# trezor_v1.net
KiCad netlist of a schematic drawn in EAGLE
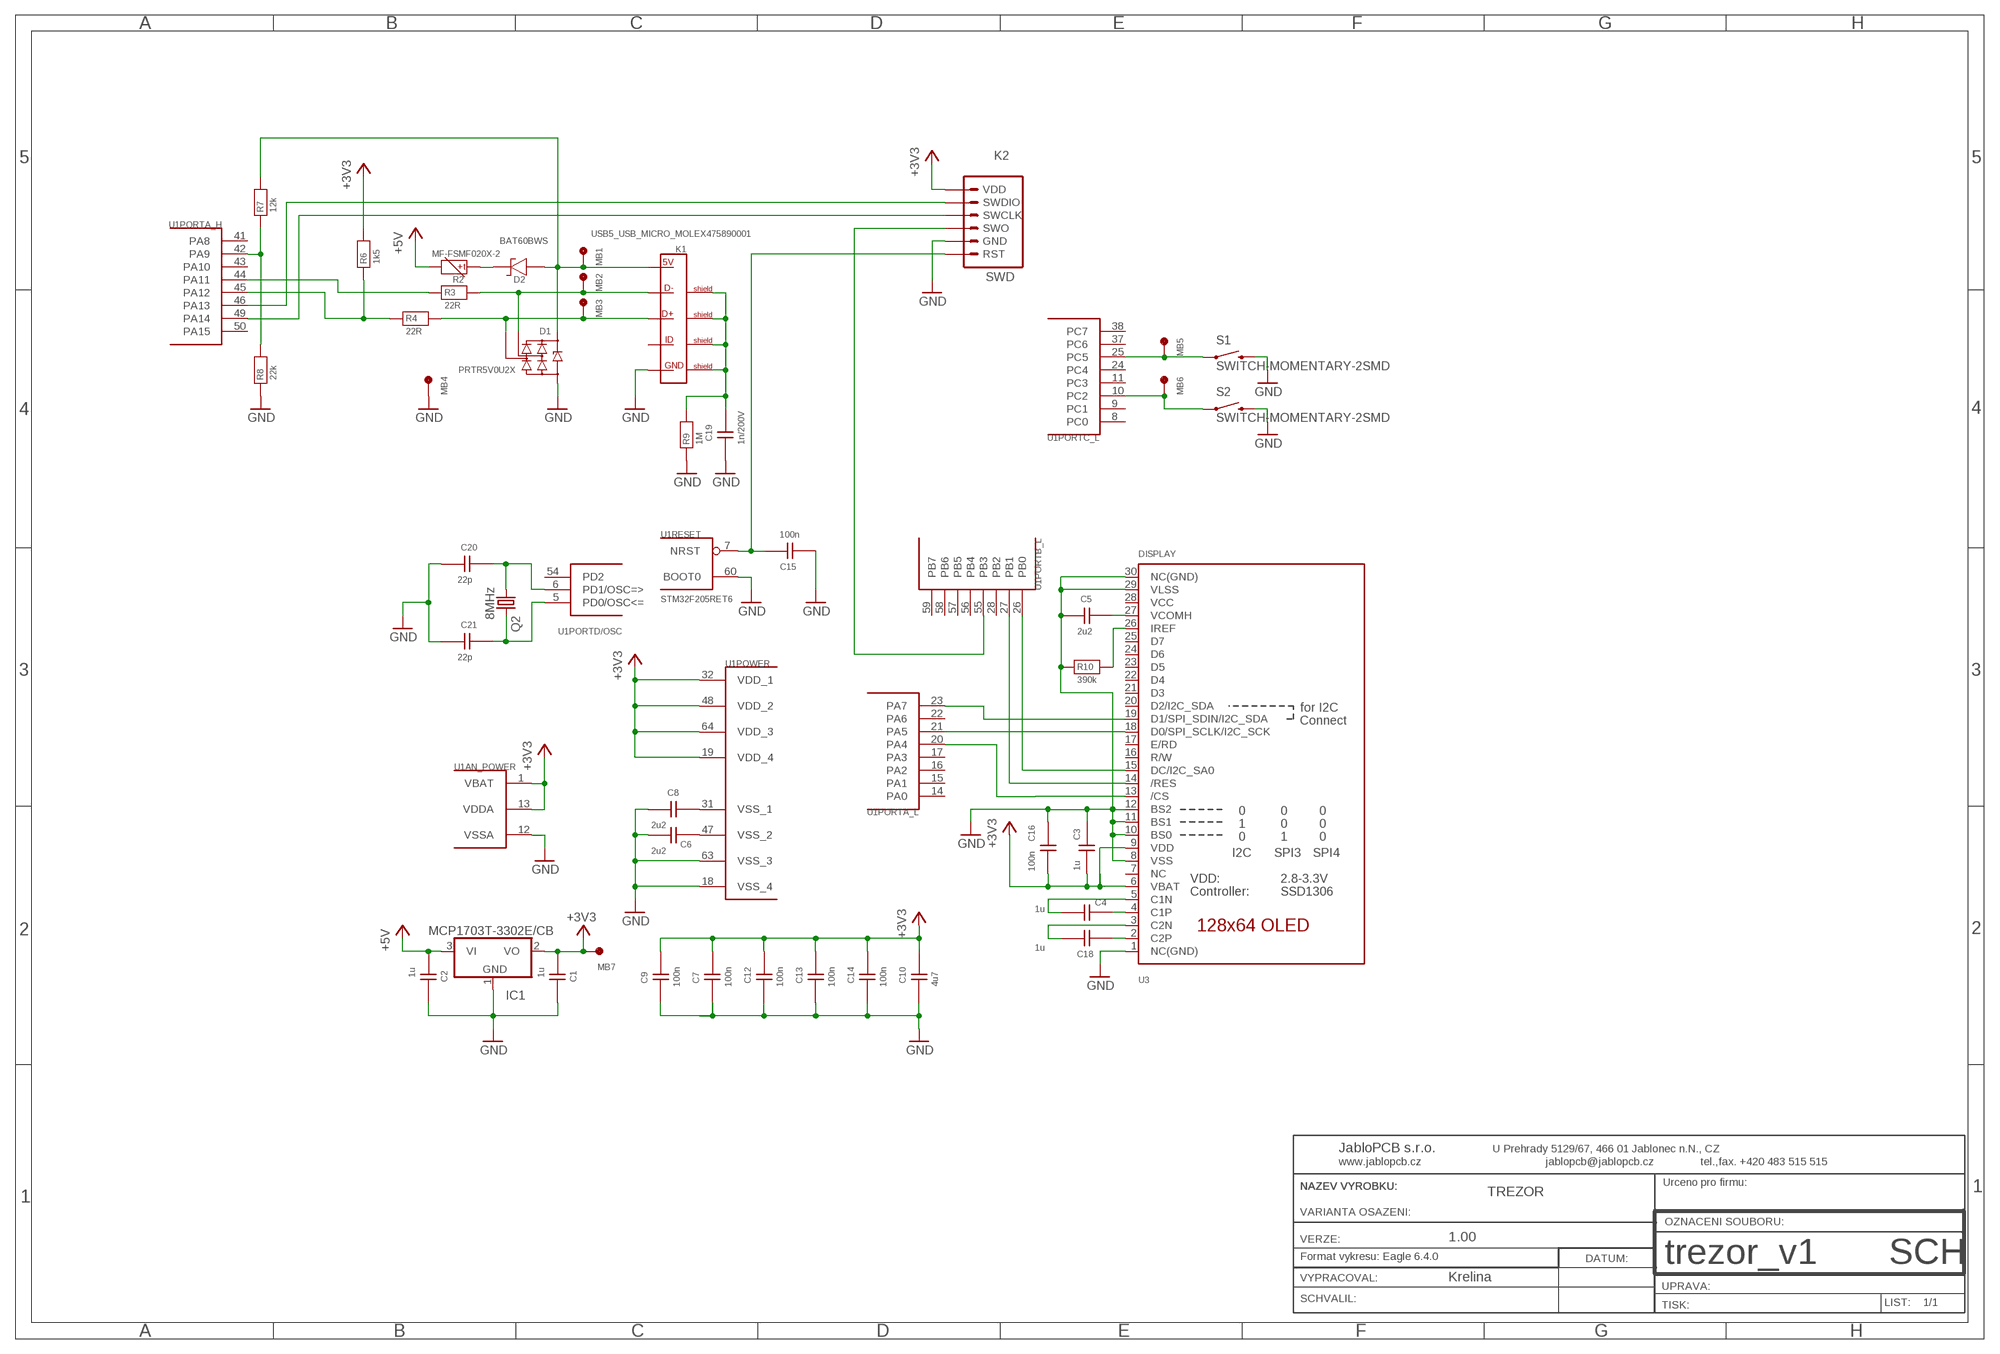
[diagram p0: schematic, sheet 1]

(export (version "E")
  (design (tool "Eeschema 10.0.6"))
  (components
    (comp (ref "C1")
      (value "1u")
      (footprint "eagle-import:0402")
      (libsource (lib "eagle-import") (part "C_0402"))
    )
    (comp (ref "C2")
      (value "1u")
      (footprint "eagle-import:0402")
      (libsource (lib "eagle-import") (part "C_0402"))
    )
    (comp (ref "C3")
      (value "1u")
      (footprint "eagle-import:0402")
      (libsource (lib "eagle-import") (part "C_0402"))
    )
    (comp (ref "C4")
      (value "1u")
      (footprint "eagle-import:0402")
      (libsource (lib "eagle-import") (part "C_0402"))
    )
    (comp (ref "C5")
      (value "2u2")
      (footprint "eagle-import:0603")
      (libsource (lib "eagle-import") (part "C_0603"))
    )
    (comp (ref "C6")
      (value "2u2")
      (footprint "eagle-import:0402")
      (libsource (lib "eagle-import") (part "C_0402"))
    )
    (comp (ref "C7")
      (value "100n")
      (footprint "eagle-import:0402")
      (libsource (lib "eagle-import") (part "C_0402"))
    )
    (comp (ref "C8")
      (value "2u2")
      (footprint "eagle-import:0402")
      (libsource (lib "eagle-import") (part "C_0402"))
    )
    (comp (ref "C9")
      (value "100n")
      (footprint "eagle-import:0402")
      (libsource (lib "eagle-import") (part "C_0402"))
    )
    (comp (ref "C10")
      (value "4u7")
      (footprint "eagle-import:0603")
      (libsource (lib "eagle-import") (part "C_0603"))
    )
    (comp (ref "C12")
      (value "100n")
      (footprint "eagle-import:0402")
      (libsource (lib "eagle-import") (part "C_0402"))
    )
    (comp (ref "C13")
      (value "100n")
      (footprint "eagle-import:0402")
      (libsource (lib "eagle-import") (part "C_0402"))
    )
    (comp (ref "C14")
      (value "100n")
      (footprint "eagle-import:0402")
      (libsource (lib "eagle-import") (part "C_0402"))
    )
    (comp (ref "C15")
      (value "100n")
      (footprint "eagle-import:0402")
      (libsource (lib "eagle-import") (part "C_0402"))
    )
    (comp (ref "C16")
      (value "100n")
      (footprint "eagle-import:0402")
      (libsource (lib "eagle-import") (part "C_0402"))
    )
    (comp (ref "C18")
      (value "1u")
      (footprint "eagle-import:0402")
      (libsource (lib "eagle-import") (part "C_0402"))
    )
    (comp (ref "C19")
      (value "1n/200V")
      (footprint "eagle-import:0603")
      (libsource (lib "eagle-import") (part "C_0603"))
    )
    (comp (ref "C20")
      (value "22p")
      (footprint "eagle-import:0402")
      (libsource (lib "eagle-import") (part "C_0402"))
    )
    (comp (ref "C21")
      (value "22p")
      (footprint "eagle-import:0402")
      (libsource (lib "eagle-import") (part "C_0402"))
    )
    (comp (ref "D1")
      (value "PRTR5V0U2X")
      (footprint "eagle-import:SOT143B")
      (libsource (lib "eagle-import") (part "PRTR5V0_SOT143B"))
    )
    (comp (ref "D2")
      (value "BAT60BWS")
      (footprint "eagle-import:SOD323")
      (libsource (lib "eagle-import") (part "DS_SOD323"))
    )
    (comp (ref "IC1")
      (value "MCP1703T-3302E/CB")
      (footprint "eagle-import:SOT23")
      (libsource (lib "eagle-import") (part "MCP1703CB"))
    )
    (comp (ref "K1")
      (value "USB5_USB_MICRO_MOLEX475890001")
      (footprint "eagle-import:USB_MICRO-MOLEX475890001")
      (libsource (lib "eagle-import") (part "USB5_USB_MICRO_MOLEX475890001"))
    )
    (comp (ref "K2")
      (value "SWD")
      (footprint "eagle-import:SWD")
      (libsource (lib "eagle-import") (part "SWD"))
    )
    (comp (ref "MB1")
      (value "MB_1.50")
      (footprint "eagle-import:MB1.5")
      (libsource (lib "eagle-import") (part "MB_1.50"))
    )
    (comp (ref "MB2")
      (value "MB_1.50")
      (footprint "eagle-import:MB1.5")
      (libsource (lib "eagle-import") (part "MB_1.50"))
    )
    (comp (ref "MB3")
      (value "MB_1.50")
      (footprint "eagle-import:MB1.5")
      (libsource (lib "eagle-import") (part "MB_1.50"))
    )
    (comp (ref "MB4")
      (value "MB_1.50")
      (footprint "eagle-import:MB1.5")
      (libsource (lib "eagle-import") (part "MB_1.50"))
    )
    (comp (ref "MB5")
      (value "MB_1.50")
      (footprint "eagle-import:MB1.5")
      (libsource (lib "eagle-import") (part "MB_1.50"))
    )
    (comp (ref "MB6")
      (value "MB_1.50")
      (footprint "eagle-import:MB1.5")
      (libsource (lib "eagle-import") (part "MB_1.50"))
    )
    (comp (ref "MB7")
      (value "MB_1.50")
      (footprint "eagle-import:MB1.5")
      (libsource (lib "eagle-import") (part "MB_1.50"))
    )
    (comp (ref "Q2")
      (value "8MHz")
      (footprint "eagle-import:CTS406")
      (libsource (lib "eagle-import") (part "CRYSTALCTS406"))
    )
    (comp (ref "R2")
      (value "MF-FSMF020X-2")
      (footprint "eagle-import:0603")
      (libsource (lib "eagle-import") (part "POLYSWITCH_0603"))
    )
    (comp (ref "R3")
      (value "22R")
      (footprint "eagle-import:0402")
      (libsource (lib "eagle-import") (part "R_0402"))
    )
    (comp (ref "R4")
      (value "22R")
      (footprint "eagle-import:0402")
      (libsource (lib "eagle-import") (part "R_0402"))
    )
    (comp (ref "R6")
      (value "1k5")
      (footprint "eagle-import:0402")
      (libsource (lib "eagle-import") (part "R_0402"))
    )
    (comp (ref "R7")
      (value "12k")
      (footprint "eagle-import:0402")
      (libsource (lib "eagle-import") (part "R_0402"))
    )
    (comp (ref "R8")
      (value "22k")
      (footprint "eagle-import:0402")
      (libsource (lib "eagle-import") (part "R_0402"))
    )
    (comp (ref "R9")
      (value "1M")
      (footprint "eagle-import:0603")
      (libsource (lib "eagle-import") (part "R_0603"))
    )
    (comp (ref "R10")
      (value "390k")
      (footprint "eagle-import:0402")
      (libsource (lib "eagle-import") (part "R_0402"))
    )
    (comp (ref "S1")
      (value "SWITCH-MOMENTARY-2SMD")
      (footprint "eagle-import:TACTILE_SWITCH_SMD")
      (libsource (lib "eagle-import") (part "SWITCH-MOMENTARY-2SMD"))
    )
    (comp (ref "S2")
      (value "SWITCH-MOMENTARY-2SMD")
      (footprint "eagle-import:TACTILE_SWITCH_SMD")
      (libsource (lib "eagle-import") (part "SWITCH-MOMENTARY-2SMD"))
    )
    (comp (ref "U1")
      (value "STM32F205RET6")
      (footprint "eagle-import:TQFP64")
      (libsource (lib "eagle-import") (part "STM32F10XRXT6"))
    )
    (comp (ref "U3")
      (value "DISPLAY")
      (footprint "eagle-import:UG-2864HSWEG01_0.96IN_WRAPAROUND")
      (libsource (lib "eagle-import") (part "DISP_OLED_UG-2864HSWEG010.96{dblquote}"))
    )
  )
  (nets
    (net (code "1") (name "+3V3") (class "Default")
      (node (ref "C1") (pin "P$1") (pinfunction "1_P$1") (pintype "passive"))
      (node (ref "C10") (pin "2") (pinfunction "2_2") (pintype "passive"))
      (node (ref "C12") (pin "P$2") (pinfunction "2_P$2") (pintype "passive"))
      (node (ref "C13") (pin "P$2") (pinfunction "2_P$2") (pintype "passive"))
      (node (ref "C14") (pin "P$2") (pinfunction "2_P$2") (pintype "passive"))
      (node (ref "C16") (pin "P$1") (pinfunction "1_P$1") (pintype "passive"))
      (node (ref "C3") (pin "P$1") (pinfunction "1_P$1") (pintype "passive"))
      (node (ref "C7") (pin "P$2") (pinfunction "2_P$2") (pintype "passive"))
      (node (ref "C9") (pin "P$2") (pinfunction "2_P$2") (pintype "passive"))
      (node (ref "IC1") (pin "2") (pinfunction "VO_2") (pintype "passive"))
      (node (ref "K2") (pin "6") (pinfunction "VDD_6") (pintype "passive"))
      (node (ref "MB7") (pin "1") (pinfunction "1_1") (pintype "passive"))
      (node (ref "R6") (pin "P$2") (pinfunction "2_P$2") (pintype "passive"))
      (node (ref "U1") (pin "1") (pinfunction "VBAT_1") (pintype "power_in"))
      (node (ref "U1") (pin "13") (pinfunction "VDDA_13") (pintype "power_in"))
      (node (ref "U1") (pin "19") (pinfunction "VDD_4_19") (pintype "power_in"))
      (node (ref "U1") (pin "32") (pinfunction "VDD_1_32") (pintype "power_in"))
      (node (ref "U1") (pin "48") (pinfunction "VDD_2_48") (pintype "power_in"))
      (node (ref "U1") (pin "64") (pinfunction "VDD_3_64") (pintype "power_in"))
      (node (ref "U3") (pin "6") (pinfunction "VBAT_6") (pintype "input"))
      (node (ref "U3") (pin "9") (pinfunction "VDD_9") (pintype "power_in"))
    )
    (net (code "2") (name "+5V") (class "Default")
      (node (ref "C2") (pin "P$1") (pinfunction "1_P$1") (pintype "passive"))
      (node (ref "IC1") (pin "3") (pinfunction "VI_3") (pintype "input"))
      (node (ref "R2") (pin "2") (pinfunction "2_2") (pintype "passive"))
    )
    (net (code "3") (name "/VCC") (class "Default")
      (node (ref "U3") (pin "28") (pinfunction "VCC_28") (pintype "power_in"))
    )
    (net (code "4") (name "GND") (class "Default")
      (node (ref "C1") (pin "P$2") (pinfunction "2_P$2") (pintype "passive"))
      (node (ref "C10") (pin "1") (pinfunction "1_1") (pintype "passive"))
      (node (ref "C12") (pin "P$1") (pinfunction "1_P$1") (pintype "passive"))
      (node (ref "C13") (pin "P$1") (pinfunction "1_P$1") (pintype "passive"))
      (node (ref "C14") (pin "P$1") (pinfunction "1_P$1") (pintype "passive"))
      (node (ref "C15") (pin "P$1") (pinfunction "1_P$1") (pintype "passive"))
      (node (ref "C16") (pin "P$2") (pinfunction "2_P$2") (pintype "passive"))
      (node (ref "C19") (pin "1") (pinfunction "1_1") (pintype "passive"))
      (node (ref "C2") (pin "P$2") (pinfunction "2_P$2") (pintype "passive"))
      (node (ref "C20") (pin "P$1") (pinfunction "1_P$1") (pintype "passive"))
      (node (ref "C21") (pin "P$1") (pinfunction "1_P$1") (pintype "passive"))
      (node (ref "C3") (pin "P$2") (pinfunction "2_P$2") (pintype "passive"))
      (node (ref "C5") (pin "1") (pinfunction "1_1") (pintype "passive"))
      (node (ref "C6") (pin "P$1") (pinfunction "1_P$1") (pintype "passive"))
      (node (ref "C7") (pin "P$1") (pinfunction "1_P$1") (pintype "passive"))
      (node (ref "C8") (pin "P$1") (pinfunction "1_P$1") (pintype "passive"))
      (node (ref "C9") (pin "P$1") (pinfunction "1_P$1") (pintype "passive"))
      (node (ref "D1") (pin "1") (pinfunction "GND_1") (pintype "passive"))
      (node (ref "IC1") (pin "1") (pinfunction "GND_1") (pintype "passive"))
      (node (ref "K1") (pin "5") (pinfunction "5_GND_5") (pintype "bidirectional"))
      (node (ref "K2") (pin "2") (pinfunction "GND_2") (pintype "passive"))
      (node (ref "MB4") (pin "1") (pinfunction "1_1") (pintype "passive"))
      (node (ref "R10") (pin "P$1") (pinfunction "1_P$1") (pintype "passive"))
      (node (ref "R8") (pin "P$1") (pinfunction "1_P$1") (pintype "passive"))
      (node (ref "R9") (pin "1") (pinfunction "1_1") (pintype "passive"))
      (node (ref "S1") (pin "3") (pinfunction "2_3") (pintype "passive"))
      (node (ref "S1") (pin "4") (pinfunction "2_4") (pintype "passive"))
      (node (ref "S2") (pin "3") (pinfunction "2_3") (pintype "passive"))
      (node (ref "S2") (pin "4") (pinfunction "2_4") (pintype "passive"))
      (node (ref "U1") (pin "12") (pinfunction "VSSA_12") (pintype "power_in"))
      (node (ref "U1") (pin "18") (pinfunction "VSS_4_18") (pintype "power_in"))
      (node (ref "U1") (pin "60") (pinfunction "BOOT0_60") (pintype "input"))
      (node (ref "U1") (pin "63") (pinfunction "VSS_3_63") (pintype "power_in"))
      (node (ref "U3") (pin "1") (pinfunction "NC(GND)_1") (pintype "input"))
      (node (ref "U3") (pin "10") (pinfunction "BS0_10") (pintype "input"))
      (node (ref "U3") (pin "11") (pinfunction "BS1_11") (pintype "input"))
      (node (ref "U3") (pin "12") (pinfunction "BS2_12") (pintype "input"))
      (node (ref "U3") (pin "29") (pinfunction "VLSS_29") (pintype "power_in"))
      (node (ref "U3") (pin "30") (pinfunction "NC(GND)_30") (pintype "input"))
      (node (ref "U3") (pin "8") (pinfunction "VSS_8") (pintype "power_in"))
    )
    (net (code "5") (name "Net-(C4-1)") (class "Default")
      (node (ref "C4") (pin "P$1") (pinfunction "1_P$1") (pintype "passive"))
      (node (ref "U3") (pin "4") (pinfunction "C1P_4") (pintype "input"))
    )
    (net (code "6") (name "Net-(C4-2)") (class "Default")
      (node (ref "C4") (pin "P$2") (pinfunction "2_P$2") (pintype "passive"))
      (node (ref "U3") (pin "5") (pinfunction "C1N_5") (pintype "input"))
    )
    (net (code "7") (name "Net-(C6-2)") (class "Default")
      (node (ref "C6") (pin "P$2") (pinfunction "2_P$2") (pintype "passive"))
      (node (ref "U1") (pin "47") (pinfunction "VSS_2_47") (pintype "power_in"))
    )
    (net (code "8") (name "Net-(C8-2)") (class "Default")
      (node (ref "C8") (pin "P$2") (pinfunction "2_P$2") (pintype "passive"))
      (node (ref "U1") (pin "31") (pinfunction "VSS_1_31") (pintype "power_in"))
    )
    (net (code "9") (name "Net-(C15-2)") (class "Default")
      (node (ref "C15") (pin "P$2") (pinfunction "2_P$2") (pintype "passive"))
      (node (ref "K2") (pin "1") (pinfunction "RST_1") (pintype "passive"))
      (node (ref "U1") (pin "7") (pinfunction "NRST_7") (pintype "input"))
    )
    (net (code "10") (name "Net-(C18-1)") (class "Default")
      (node (ref "C18") (pin "P$1") (pinfunction "1_P$1") (pintype "passive"))
      (node (ref "U3") (pin "2") (pinfunction "C2P_2") (pintype "input"))
    )
    (net (code "11") (name "Net-(C18-2)") (class "Default")
      (node (ref "C18") (pin "P$2") (pinfunction "2_P$2") (pintype "passive"))
      (node (ref "U3") (pin "3") (pinfunction "C2N_3") (pintype "input"))
    )
    (net (code "12") (name "Net-(C19-Pad2)") (class "Default")
      (node (ref "C19") (pin "2") (pinfunction "2_2") (pintype "passive"))
      (node (ref "K1") (pin "S1_BOT") (pinfunction "SHIELD_1_S1_BOT") (pintype "passive"))
      (node (ref "K1") (pin "S1_TOP") (pinfunction "SHIELD_1_S1_TOP") (pintype "passive"))
      (node (ref "K1") (pin "S2_BOT") (pinfunction "SHIELD_2_S2_BOT") (pintype "passive"))
      (node (ref "K1") (pin "S2_TOP") (pinfunction "SHIELD_2_S2_TOP") (pintype "passive"))
      (node (ref "K1") (pin "S3_BOT") (pinfunction "SHIELD_3_S3_BOT") (pintype "passive"))
      (node (ref "K1") (pin "S3_TOP") (pinfunction "SHIELD_3_S3_TOP") (pintype "passive"))
      (node (ref "K1") (pin "S4_BOT") (pinfunction "SHIELD_4_S4_BOT") (pintype "passive"))
      (node (ref "K1") (pin "S4_TOP") (pinfunction "SHIELD_4_S4_TOP") (pintype "passive"))
      (node (ref "K1") (pin "SA") (pinfunction "SHIELD_1_SA") (pintype "passive"))
      (node (ref "K1") (pin "SB") (pinfunction "SHIELD_2_SB") (pintype "passive"))
      (node (ref "R9") (pin "2") (pinfunction "2_2") (pintype "passive"))
    )
    (net (code "13") (name "Net-(C20-2)") (class "Default")
      (node (ref "C20") (pin "P$2") (pinfunction "2_P$2") (pintype "passive"))
      (node (ref "Q2") (pin "1") (pinfunction "1_1") (pintype "passive"))
      (node (ref "U1") (pin "6") (pinfunction "PD1/OSC=>_6") (pintype "bidirectional"))
    )
    (net (code "14") (name "Net-(C21-2)") (class "Default")
      (node (ref "C21") (pin "P$2") (pinfunction "2_P$2") (pintype "passive"))
      (node (ref "Q2") (pin "3") (pinfunction "2_3") (pintype "passive"))
      (node (ref "U1") (pin "5") (pinfunction "PD0/OSC<=_5") (pintype "bidirectional"))
    )
    (net (code "15") (name "Net-(D1-I{slash}O1)") (class "Default")
      (node (ref "D1") (pin "2") (pinfunction "I/O1_2") (pintype "passive"))
      (node (ref "K1") (pin "2") (pinfunction "2_D-_2") (pintype "bidirectional"))
      (node (ref "MB2") (pin "1") (pinfunction "1_1") (pintype "passive"))
      (node (ref "R3") (pin "P$2") (pinfunction "2_P$2") (pintype "passive"))
    )
    (net (code "16") (name "Net-(D1-I{slash}O2)") (class "Default")
      (node (ref "D1") (pin "3") (pinfunction "I/O2_3") (pintype "passive"))
      (node (ref "K1") (pin "3") (pinfunction "3_D+_3") (pintype "bidirectional"))
      (node (ref "MB3") (pin "1") (pinfunction "1_1") (pintype "passive"))
      (node (ref "R4") (pin "P$2") (pinfunction "2_P$2") (pintype "passive"))
    )
    (net (code "17") (name "Net-(D1-VCC)") (class "Default")
      (node (ref "D1") (pin "4") (pinfunction "VCC_4") (pintype "passive"))
      (node (ref "D2") (pin "A") (pinfunction "1_A") (pintype "passive"))
      (node (ref "K1") (pin "1") (pinfunction "1_5V_1") (pintype "bidirectional"))
      (node (ref "MB1") (pin "1") (pinfunction "1_1") (pintype "passive"))
      (node (ref "R7") (pin "P$2") (pinfunction "2_P$2") (pintype "passive"))
    )
    (net (code "18") (name "Net-(D2-2)") (class "Default")
      (node (ref "D2") (pin "K") (pinfunction "2_K") (pintype "passive"))
      (node (ref "R2") (pin "1") (pinfunction "1_1") (pintype "passive"))
    )
    (net (code "19") (name "Net-(K2-SWCLK)") (class "Default")
      (node (ref "K2") (pin "4") (pinfunction "SWCLK_4") (pintype "passive"))
      (node (ref "U1") (pin "49") (pinfunction "PA14_49") (pintype "bidirectional"))
    )
    (net (code "20") (name "Net-(K2-SWDIO)") (class "Default")
      (node (ref "K2") (pin "5") (pinfunction "SWDIO_5") (pintype "passive"))
      (node (ref "U1") (pin "46") (pinfunction "PA13_46") (pintype "bidirectional"))
    )
    (net (code "21") (name "Net-(K2-SWO)") (class "Default")
      (node (ref "K2") (pin "3") (pinfunction "SWO_3") (pintype "passive"))
      (node (ref "U1") (pin "55") (pinfunction "PB3_55") (pintype "bidirectional"))
    )
    (net (code "22") (name "Net-(R3-1)") (class "Default")
      (node (ref "R3") (pin "P$1") (pinfunction "1_P$1") (pintype "passive"))
      (node (ref "U1") (pin "44") (pinfunction "PA11_44") (pintype "bidirectional"))
    )
    (net (code "23") (name "Net-(R4-1)") (class "Default")
      (node (ref "R4") (pin "P$1") (pinfunction "1_P$1") (pintype "passive"))
      (node (ref "R6") (pin "P$1") (pinfunction "1_P$1") (pintype "passive"))
      (node (ref "U1") (pin "45") (pinfunction "PA12_45") (pintype "bidirectional"))
    )
    (net (code "24") (name "Net-(R7-1)") (class "Default")
      (node (ref "R7") (pin "P$1") (pinfunction "1_P$1") (pintype "passive"))
      (node (ref "R8") (pin "P$2") (pinfunction "2_P$2") (pintype "passive"))
      (node (ref "U1") (pin "42") (pinfunction "PA9_42") (pintype "bidirectional"))
    )
    (net (code "25") (name "Net-(R10-2)") (class "Default")
      (node (ref "R10") (pin "P$2") (pinfunction "2_P$2") (pintype "passive"))
      (node (ref "U3") (pin "26") (pinfunction "IREF_26") (pintype "input"))
    )
    (net (code "26") (name "Net-(U1C-PA4)") (class "Default")
      (node (ref "U1") (pin "20") (pinfunction "PA4_20") (pintype "bidirectional"))
      (node (ref "U3") (pin "13") (pinfunction "/CS_13") (pintype "input"))
    )
    (net (code "27") (name "Net-(U1C-PA5)") (class "Default")
      (node (ref "U1") (pin "21") (pinfunction "PA5_21") (pintype "bidirectional"))
      (node (ref "U3") (pin "18") (pinfunction "D0/SPI_SCLK/I2C_SCK_18") (pintype "bidirectional"))
    )
    (net (code "28") (name "Net-(U1C-PA7)") (class "Default")
      (node (ref "U1") (pin "23") (pinfunction "PA7_23") (pintype "bidirectional"))
      (node (ref "U3") (pin "19") (pinfunction "D1/SPI_SDIN/I2C_SDA_19") (pintype "bidirectional"))
    )
    (net (code "29") (name "Net-(U1E-PB0)") (class "Default")
      (node (ref "U1") (pin "26") (pinfunction "PB0_26") (pintype "bidirectional"))
      (node (ref "U3") (pin "15") (pinfunction "DC/I2C_SA0_15") (pintype "input"))
    )
    (net (code "30") (name "Net-(U1E-PB1)") (class "Default")
      (node (ref "U1") (pin "27") (pinfunction "PB1_27") (pintype "bidirectional"))
      (node (ref "U3") (pin "14") (pinfunction "/RES_14") (pintype "input"))
    )
    (net (code "31") (name "Net-(U1G-PC2)") (class "Default")
      (node (ref "MB6") (pin "1") (pinfunction "1_1") (pintype "passive"))
      (node (ref "S2") (pin "1") (pinfunction "1_1") (pintype "passive"))
      (node (ref "S2") (pin "2") (pinfunction "1_2") (pintype "passive"))
      (node (ref "U1") (pin "10") (pinfunction "PC2_10") (pintype "bidirectional"))
    )
    (net (code "32") (name "Net-(U1G-PC5)") (class "Default")
      (node (ref "MB5") (pin "1") (pinfunction "1_1") (pintype "passive"))
      (node (ref "S1") (pin "1") (pinfunction "1_1") (pintype "passive"))
      (node (ref "S1") (pin "2") (pinfunction "1_2") (pintype "passive"))
      (node (ref "U1") (pin "25") (pinfunction "PC5_25") (pintype "bidirectional"))
    )
    (net (code "33") (name "Net-(U3-VCOMH)") (class "Default")
      (node (ref "C5") (pin "2") (pinfunction "2_2") (pintype "passive"))
      (node (ref "U3") (pin "27") (pinfunction "VCOMH_27") (pintype "output"))
    )
    (net (code "34") (name "unconnected-(K1-4_ID-Pad4)") (class "Default")
      (node (ref "K1") (pin "4") (pinfunction "4_ID_4") (pintype "bidirectional"))
    )
    (net (code "35") (name "unconnected-(U1B-PA8-Pad41)") (class "Default")
      (node (ref "U1") (pin "41") (pinfunction "PA8_41") (pintype "bidirectional"))
    )
    (net (code "36") (name "unconnected-(U1B-PA10-Pad43)") (class "Default")
      (node (ref "U1") (pin "43") (pinfunction "PA10_43") (pintype "bidirectional"))
    )
    (net (code "37") (name "unconnected-(U1B-PA15-Pad50)") (class "Default")
      (node (ref "U1") (pin "50") (pinfunction "PA15_50") (pintype "bidirectional"))
    )
    (net (code "38") (name "unconnected-(U1C-PA0-Pad14)") (class "Default")
      (node (ref "U1") (pin "14") (pinfunction "PA0_14") (pintype "bidirectional"))
    )
    (net (code "39") (name "unconnected-(U1C-PA1-Pad15)") (class "Default")
      (node (ref "U1") (pin "15") (pinfunction "PA1_15") (pintype "bidirectional"))
    )
    (net (code "40") (name "unconnected-(U1C-PA2-Pad16)") (class "Default")
      (node (ref "U1") (pin "16") (pinfunction "PA2_16") (pintype "bidirectional"))
    )
    (net (code "41") (name "unconnected-(U1C-PA3-Pad17)") (class "Default")
      (node (ref "U1") (pin "17") (pinfunction "PA3_17") (pintype "bidirectional"))
    )
    (net (code "42") (name "unconnected-(U1C-PA6-Pad22)") (class "Default")
      (node (ref "U1") (pin "22") (pinfunction "PA6_22") (pintype "bidirectional"))
    )
    (net (code "43") (name "unconnected-(U1E-PB2-Pad28)") (class "Default")
      (node (ref "U1") (pin "28") (pinfunction "PB2_28") (pintype "bidirectional"))
    )
    (net (code "44") (name "unconnected-(U1E-PB4-Pad56)") (class "Default")
      (node (ref "U1") (pin "56") (pinfunction "PB4_56") (pintype "bidirectional"))
    )
    (net (code "45") (name "unconnected-(U1E-PB5-Pad57)") (class "Default")
      (node (ref "U1") (pin "57") (pinfunction "PB5_57") (pintype "bidirectional"))
    )
    (net (code "46") (name "unconnected-(U1E-PB6-Pad58)") (class "Default")
      (node (ref "U1") (pin "58") (pinfunction "PB6_58") (pintype "bidirectional"))
    )
    (net (code "47") (name "unconnected-(U1E-PB7-Pad59)") (class "Default")
      (node (ref "U1") (pin "59") (pinfunction "PB7_59") (pintype "bidirectional"))
    )
    (net (code "48") (name "unconnected-(U1G-PC0-Pad8)") (class "Default")
      (node (ref "U1") (pin "8") (pinfunction "PC0_8") (pintype "bidirectional"))
    )
    (net (code "49") (name "unconnected-(U1G-PC1-Pad9)") (class "Default")
      (node (ref "U1") (pin "9") (pinfunction "PC1_9") (pintype "bidirectional"))
    )
    (net (code "50") (name "unconnected-(U1G-PC3-Pad11)") (class "Default")
      (node (ref "U1") (pin "11") (pinfunction "PC3_11") (pintype "bidirectional"))
    )
    (net (code "51") (name "unconnected-(U1G-PC4-Pad24)") (class "Default")
      (node (ref "U1") (pin "24") (pinfunction "PC4_24") (pintype "bidirectional"))
    )
    (net (code "52") (name "unconnected-(U1G-PC6-Pad37)") (class "Default")
      (node (ref "U1") (pin "37") (pinfunction "PC6_37") (pintype "bidirectional"))
    )
    (net (code "53") (name "unconnected-(U1G-PC7-Pad38)") (class "Default")
      (node (ref "U1") (pin "38") (pinfunction "PC7_38") (pintype "bidirectional"))
    )
    (net (code "54") (name "unconnected-(U1H-PD2-Pad54)") (class "Default")
      (node (ref "U1") (pin "54") (pinfunction "PD2_54") (pintype "bidirectional"))
    )
    (net (code "55") (name "unconnected-(U3-D2{slash}I2C_SDA-Pad20)") (class "Default")
      (node (ref "U3") (pin "20") (pinfunction "D2/I2C_SDA_20") (pintype "bidirectional"))
    )
    (net (code "56") (name "unconnected-(U3-D3-Pad21)") (class "Default")
      (node (ref "U3") (pin "21") (pinfunction "D3_21") (pintype "bidirectional"))
    )
    (net (code "57") (name "unconnected-(U3-D4-Pad22)") (class "Default")
      (node (ref "U3") (pin "22") (pinfunction "D4_22") (pintype "bidirectional"))
    )
    (net (code "58") (name "unconnected-(U3-D5-Pad23)") (class "Default")
      (node (ref "U3") (pin "23") (pinfunction "D5_23") (pintype "bidirectional"))
    )
    (net (code "59") (name "unconnected-(U3-D6-Pad24)") (class "Default")
      (node (ref "U3") (pin "24") (pinfunction "D6_24") (pintype "bidirectional"))
    )
    (net (code "60") (name "unconnected-(U3-D7-Pad25)") (class "Default")
      (node (ref "U3") (pin "25") (pinfunction "D7_25") (pintype "bidirectional"))
    )
    (net (code "61") (name "unconnected-(U3-E{slash}RD-Pad17)") (class "Default")
      (node (ref "U3") (pin "17") (pinfunction "E/RD_17") (pintype "input"))
    )
    (net (code "62") (name "unconnected-(U3-NC-Pad7)") (class "Default")
      (node (ref "U3") (pin "7") (pinfunction "NC_7") (pintype "no_connect"))
    )
    (net (code "63") (name "unconnected-(U3-R{slash}W-Pad16)") (class "Default")
      (node (ref "U3") (pin "16") (pinfunction "R/W_16") (pintype "input"))
    )
  )
)
